# kibannISE2024_contral.net
KiCad netlist of a schematic drawn in EAGLE
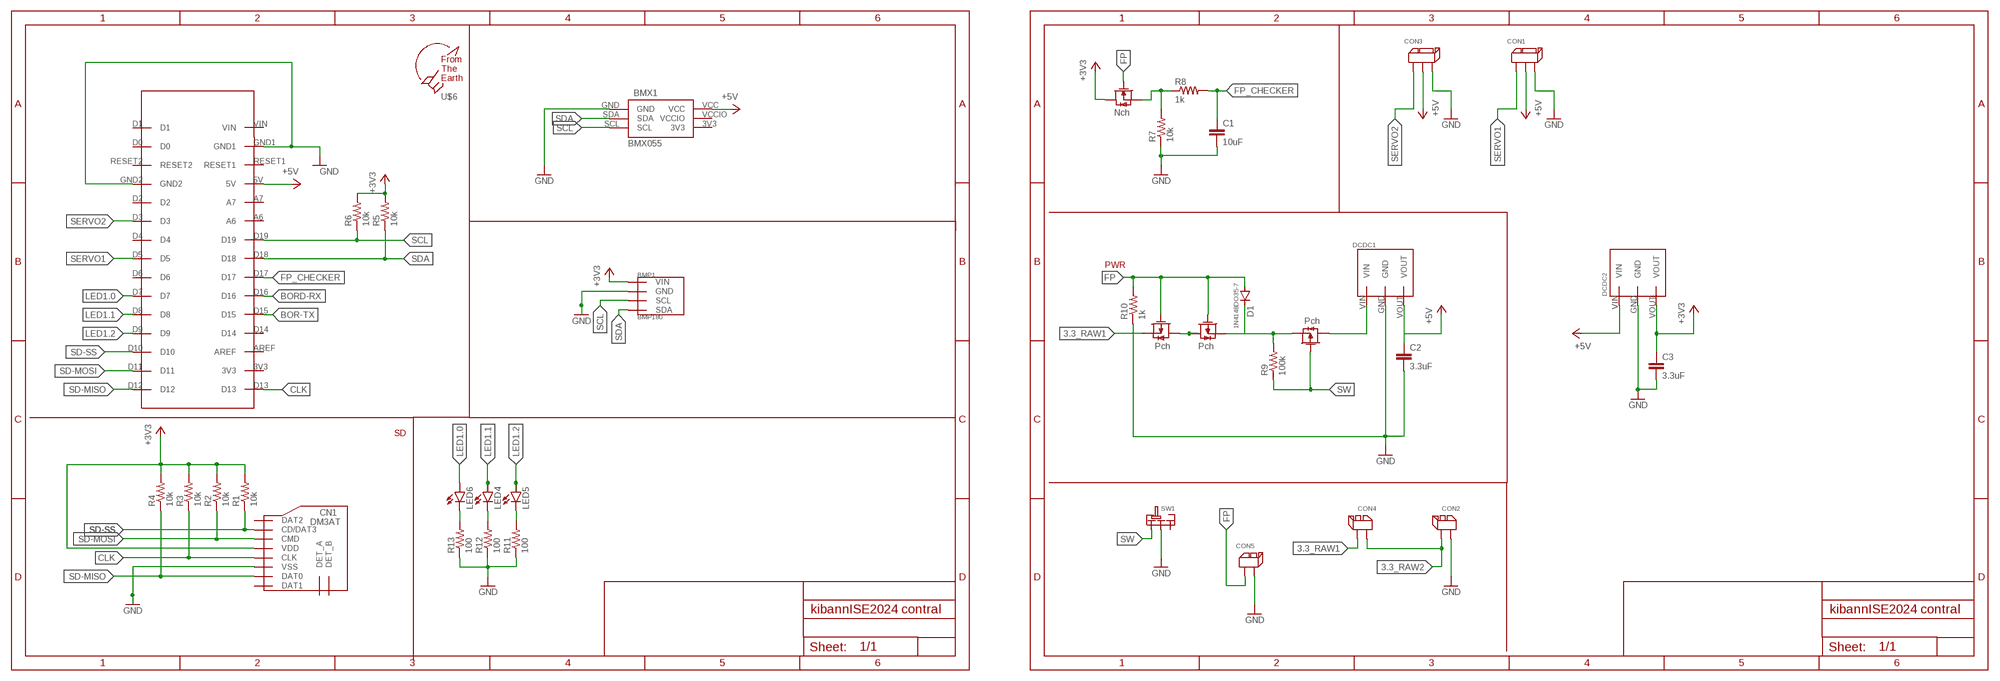
[diagram p0: schematic, sheet 1]

(export (version "E")
  (design (tool "Eeschema 10.0.6"))
  (components
    (comp (ref "BMP1")
      (value "BMP180")
      (footprint "eagle-import:GY-68")
      (libsource (lib "eagle-import") (part "BMP180"))
    )
    (comp (ref "BMX1")
      (value "BMX055")
      (footprint "eagle-import:BMX055")
      (libsource (lib "eagle-import") (part "BMX055"))
    )
    (comp (ref "C1")
      (value "10uF")
      (footprint "eagle-import:C025-024X044")
      (libsource (lib "eagle-import") (part "C-EU025-024X044"))
    )
    (comp (ref "C2")
      (value "3.3uF")
      (footprint "eagle-import:C025-024X044")
      (libsource (lib "eagle-import") (part "C-EU025-024X044"))
    )
    (comp (ref "C3")
      (value "3.3uF")
      (footprint "eagle-import:C025-024X044")
      (libsource (lib "eagle-import") (part "C-EU025-024X044"))
    )
    (comp (ref "CN1")
      (value "DM3AT")
      (footprint "eagle-import:DM3AT")
      (libsource (lib "eagle-import") (part "DM3AT"))
    )
    (comp (ref "CON1")
      (value "3PIN")
      (footprint "eagle-import:3PIN")
      (libsource (lib "eagle-import") (part "3PIN"))
    )
    (comp (ref "CON2")
      (value "2PIN")
      (footprint "eagle-import:2PIN")
      (libsource (lib "eagle-import") (part "2PIN"))
    )
    (comp (ref "CON3")
      (value "3PIN")
      (footprint "eagle-import:3PIN")
      (libsource (lib "eagle-import") (part "3PIN"))
    )
    (comp (ref "CON4")
      (value "2PIN")
      (footprint "eagle-import:2PIN")
      (libsource (lib "eagle-import") (part "2PIN"))
    )
    (comp (ref "CON5")
      (value "2PIN")
      (footprint "eagle-import:2PIN")
      (libsource (lib "eagle-import") (part "2PIN"))
    )
    (comp (ref "D1")
      (value "1N4148DO35-7")
      (footprint "eagle-import:DO35-7")
      (libsource (lib "eagle-import") (part "1N4148DO35-7"))
    )
    (comp (ref "DCDC1")
      (value "5V1A_M78AR05-1")
      (footprint "eagle-import:5V1A_M78AR05-1")
      (libsource (lib "eagle-import") (part "5V1A_M78AR05-1"))
    )
    (comp (ref "DCDC2")
      (value "3.3V1A_M78AR033-1")
      (footprint "eagle-import:3.3V1A_M78AR033-1")
      (libsource (lib "eagle-import") (part "3.3V1A_M78AR033-1"))
    )
    (comp (ref "LED4")
      (value "LED5MM")
      (footprint "eagle-import:LED5MM")
      (libsource (lib "eagle-import") (part "LED5MM"))
    )
    (comp (ref "LED5")
      (value "LED5MM")
      (footprint "eagle-import:LED5MM")
      (libsource (lib "eagle-import") (part "LED5MM"))
    )
    (comp (ref "LED6")
      (value "LED5MM")
      (footprint "eagle-import:LED5MM")
      (libsource (lib "eagle-import") (part "LED5MM"))
    )
    (comp (ref "R1")
      (value "10k")
      (footprint "eagle-import:0204_7")
      (libsource (lib "eagle-import") (part "R-US_0204/7"))
    )
    (comp (ref "R2")
      (value "10k")
      (footprint "eagle-import:0204_7")
      (libsource (lib "eagle-import") (part "R-US_0204/7"))
    )
    (comp (ref "R3")
      (value "10k")
      (footprint "eagle-import:0204_7")
      (libsource (lib "eagle-import") (part "R-US_0204/7"))
    )
    (comp (ref "R4")
      (value "10k")
      (footprint "eagle-import:0204_7")
      (libsource (lib "eagle-import") (part "R-US_0204/7"))
    )
    (comp (ref "R5")
      (value "10k")
      (footprint "eagle-import:0204_7")
      (libsource (lib "eagle-import") (part "R-US_0204/7"))
    )
    (comp (ref "R6")
      (value "10k")
      (footprint "eagle-import:0204_7")
      (libsource (lib "eagle-import") (part "R-US_0204/7"))
    )
    (comp (ref "R7")
      (value "10k")
      (footprint "eagle-import:0204_7")
      (libsource (lib "eagle-import") (part "R-US_0204/7"))
    )
    (comp (ref "R8")
      (value "1k")
      (footprint "eagle-import:0204_7")
      (libsource (lib "eagle-import") (part "R-US_0204/7"))
    )
    (comp (ref "R9")
      (value "100k")
      (footprint "eagle-import:0204_7")
      (libsource (lib "eagle-import") (part "R-US_0204/7"))
    )
    (comp (ref "R10")
      (value "1k")
      (footprint "eagle-import:0204_7")
      (libsource (lib "eagle-import") (part "R-US_0204/7"))
    )
    (comp (ref "R11")
      (value "100")
      (footprint "eagle-import:0204_7")
      (libsource (lib "eagle-import") (part "R-US_0204/7"))
    )
    (comp (ref "R12")
      (value "100")
      (footprint "eagle-import:0204_7")
      (libsource (lib "eagle-import") (part "R-US_0204/7"))
    )
    (comp (ref "R13")
      (value "100")
      (footprint "eagle-import:0204_7")
      (libsource (lib "eagle-import") (part "R-US_0204/7"))
    )
    (comp (ref "SW1")
      (value "SRIDE_SWITCH")
      (footprint "eagle-import:SRIDE_SWITCH")
      (libsource (lib "eagle-import") (part "SRIDE_SWITCH"))
    )
    (comp (ref "U$1")
      (value "ARDUINONANO")
      (footprint "eagle-import:ARDUINONANO")
      (libsource (lib "eagle-import") (part "ARDUINONANO"))
    )
    (comp (ref "U$2")
      (value "2SJ681-PCH")
      (footprint "eagle-import:2SJ681")
      (libsource (lib "eagle-import") (part "2SJ681-PCH"))
    )
    (comp (ref "U$3")
      (value "2SK4017-NCH")
      (footprint "eagle-import:2SK4017")
      (libsource (lib "eagle-import") (part "2SK4017-NCH"))
    )
    (comp (ref "U$4")
      (value "2SJ681-PCH")
      (footprint "eagle-import:2SJ681")
      (libsource (lib "eagle-import") (part "2SJ681-PCH"))
    )
    (comp (ref "U$5")
      (value "2SJ681-PCH")
      (footprint "eagle-import:2SJ681")
      (libsource (lib "eagle-import") (part "2SJ681-PCH"))
    )
    (comp (ref "U$6")
      (value "F.T.E.LOGO")
      (footprint "eagle-import:LOGO")
      (libsource (lib "eagle-import") (part "F.T.E.LOGO"))
    )
  )
  (nets
    (net (code "1") (name "+3V3") (class "Default")
      (node (ref "BMP1") (pin "P1") (pinfunction "VIN_P1") (pintype "bidirectional"))
      (node (ref "C3") (pin "1") (pinfunction "1_1") (pintype "passive"))
      (node (ref "CN1") (pin "VDD") (pinfunction "VDD_VDD") (pintype "bidirectional"))
      (node (ref "DCDC2") (pin "VOUT") (pinfunction "VOUT_VOUT") (pintype "bidirectional"))
      (node (ref "R1") (pin "2") (pinfunction "2_2") (pintype "passive"))
      (node (ref "R2") (pin "2") (pinfunction "2_2") (pintype "passive"))
      (node (ref "R3") (pin "2") (pinfunction "2_2") (pintype "passive"))
      (node (ref "R4") (pin "2") (pinfunction "2_2") (pintype "passive"))
      (node (ref "R5") (pin "2") (pinfunction "2_2") (pintype "passive"))
      (node (ref "R6") (pin "2") (pinfunction "2_2") (pintype "passive"))
      (node (ref "U$3") (pin "DRAIN") (pinfunction "DRAIN_DRAIN") (pintype "bidirectional"))
    )
    (net (code "2") (name "+5V") (class "Default")
      (node (ref "BMX1") (pin "VCC") (pinfunction "VCC_VCC") (pintype "power_in"))
      (node (ref "C2") (pin "1") (pinfunction "1_1") (pintype "passive"))
      (node (ref "CON1") (pin "P$2") (pinfunction "P$2_P$2") (pintype "bidirectional"))
      (node (ref "CON3") (pin "P$2") (pinfunction "P$2_P$2") (pintype "bidirectional"))
      (node (ref "DCDC1") (pin "VOUT") (pinfunction "VOUT_VOUT") (pintype "bidirectional"))
      (node (ref "DCDC2") (pin "VIN") (pinfunction "VIN_VIN") (pintype "bidirectional"))
      (node (ref "U$1") (pin "5V") (pinfunction "5V_5V") (pintype "bidirectional"))
    )
    (net (code "3") (name "/3V3") (class "Default")
      (node (ref "BMX1") (pin "3V3") (pinfunction "3V3_3V3") (pintype "power_in"))
    )
    (net (code "4") (name "/VCCIO") (class "Default")
      (node (ref "BMX1") (pin "VCCIO") (pinfunction "VCCIO_VCCIO") (pintype "power_in"))
    )
    (net (code "5") (name "3.3_RAW1") (class "Default")
      (node (ref "CON4") (pin "P$2") (pinfunction "P$2_P$2") (pintype "bidirectional"))
      (node (ref "U$2") (pin "SOURCE") (pinfunction "SOURCE_SOURCE") (pintype "bidirectional"))
    )
    (net (code "6") (name "3.3_RAW2") (class "Default")
      (node (ref "CON2") (pin "P$2") (pinfunction "P$2_P$2") (pintype "bidirectional"))
      (node (ref "CON4") (pin "P$1") (pinfunction "P$1_P$1") (pintype "bidirectional"))
    )
    (net (code "7") (name "BOR-TX") (class "Default")
      (node (ref "U$1") (pin "D15") (pinfunction "D15_D15") (pintype "bidirectional"))
    )
    (net (code "8") (name "BORD-RX") (class "Default")
      (node (ref "U$1") (pin "D16") (pinfunction "D16_D16") (pintype "bidirectional"))
    )
    (net (code "9") (name "CLK") (class "Default")
      (node (ref "CN1") (pin "CLK") (pinfunction "CLK_CLK") (pintype "bidirectional"))
      (node (ref "R3") (pin "1") (pinfunction "1_1") (pintype "passive"))
      (node (ref "U$1") (pin "D13") (pinfunction "D13_D13") (pintype "bidirectional"))
    )
    (net (code "10") (name "FP") (class "Default")
      (node (ref "CON5") (pin "P$1") (pinfunction "P$1_P$1") (pintype "bidirectional"))
      (node (ref "D1") (pin "A") (pinfunction "A_A") (pintype "passive"))
      (node (ref "R10") (pin "2") (pinfunction "2_2") (pintype "passive"))
      (node (ref "U$2") (pin "GATE") (pinfunction "GATE_GATE") (pintype "bidirectional"))
      (node (ref "U$3") (pin "GATE") (pinfunction "GATE_GATE") (pintype "bidirectional"))
      (node (ref "U$4") (pin "GATE") (pinfunction "GATE_GATE") (pintype "bidirectional"))
    )
    (net (code "11") (name "FP_CHECKER") (class "Default")
      (node (ref "C1") (pin "1") (pinfunction "1_1") (pintype "passive"))
      (node (ref "R8") (pin "2") (pinfunction "2_2") (pintype "passive"))
      (node (ref "U$1") (pin "D17") (pinfunction "D17_D17") (pintype "bidirectional"))
    )
    (net (code "12") (name "GND") (class "Default")
      (node (ref "BMP1") (pin "P2") (pinfunction "GND_P2") (pintype "bidirectional"))
      (node (ref "BMX1") (pin "GND") (pinfunction "GND_GND") (pintype "power_in"))
      (node (ref "C1") (pin "2") (pinfunction "2_2") (pintype "passive"))
      (node (ref "C2") (pin "2") (pinfunction "2_2") (pintype "passive"))
      (node (ref "C3") (pin "2") (pinfunction "2_2") (pintype "passive"))
      (node (ref "CN1") (pin "VSS") (pinfunction "VSS_VSS") (pintype "bidirectional"))
      (node (ref "CON1") (pin "P$3") (pinfunction "P$3_P$3") (pintype "bidirectional"))
      (node (ref "CON2") (pin "P$1") (pinfunction "P$1_P$1") (pintype "bidirectional"))
      (node (ref "CON3") (pin "P$3") (pinfunction "P$3_P$3") (pintype "bidirectional"))
      (node (ref "CON5") (pin "P$2") (pinfunction "P$2_P$2") (pintype "bidirectional"))
      (node (ref "DCDC1") (pin "GND") (pinfunction "GND_GND") (pintype "bidirectional"))
      (node (ref "DCDC2") (pin "GND") (pinfunction "GND_GND") (pintype "bidirectional"))
      (node (ref "R10") (pin "1") (pinfunction "1_1") (pintype "passive"))
      (node (ref "R11") (pin "1") (pinfunction "1_1") (pintype "passive"))
      (node (ref "R12") (pin "1") (pinfunction "1_1") (pintype "passive"))
      (node (ref "R13") (pin "1") (pinfunction "1_1") (pintype "passive"))
      (node (ref "R7") (pin "1") (pinfunction "1_1") (pintype "passive"))
      (node (ref "SW1") (pin "LR") (pinfunction "LR_LR") (pintype "bidirectional"))
      (node (ref "U$1") (pin "GND1") (pinfunction "GND1_GND1") (pintype "bidirectional"))
      (node (ref "U$1") (pin "GND2") (pinfunction "GND2_GND2") (pintype "bidirectional"))
    )
    (net (code "13") (name "LED1.0") (class "Default")
      (node (ref "LED6") (pin "A") (pinfunction "A_A") (pintype "passive"))
      (node (ref "U$1") (pin "D7") (pinfunction "D7_D7") (pintype "bidirectional"))
    )
    (net (code "14") (name "LED1.1") (class "Default")
      (node (ref "LED4") (pin "A") (pinfunction "A_A") (pintype "passive"))
      (node (ref "U$1") (pin "D8") (pinfunction "D8_D8") (pintype "bidirectional"))
    )
    (net (code "15") (name "LED1.2") (class "Default")
      (node (ref "LED5") (pin "A") (pinfunction "A_A") (pintype "passive"))
      (node (ref "U$1") (pin "D9") (pinfunction "D9_D9") (pintype "bidirectional"))
    )
    (net (code "16") (name "Net-(D1-PadC)") (class "Default")
      (node (ref "D1") (pin "C") (pinfunction "C_C") (pintype "passive"))
      (node (ref "R9") (pin "2") (pinfunction "2_2") (pintype "passive"))
      (node (ref "U$4") (pin "SOURCE") (pinfunction "SOURCE_SOURCE") (pintype "bidirectional"))
      (node (ref "U$5") (pin "SOURCE") (pinfunction "SOURCE_SOURCE") (pintype "bidirectional"))
    )
    (net (code "17") (name "Net-(DCDC1-PadVIN)") (class "Default")
      (node (ref "DCDC1") (pin "VIN") (pinfunction "VIN_VIN") (pintype "bidirectional"))
      (node (ref "U$5") (pin "DRAIN") (pinfunction "DRAIN_DRAIN") (pintype "bidirectional"))
    )
    (net (code "18") (name "Net-(LED4-C)") (class "Default")
      (node (ref "LED4") (pin "K") (pinfunction "C_K") (pintype "passive"))
      (node (ref "R12") (pin "2") (pinfunction "2_2") (pintype "passive"))
    )
    (net (code "19") (name "Net-(LED5-C)") (class "Default")
      (node (ref "LED5") (pin "K") (pinfunction "C_K") (pintype "passive"))
      (node (ref "R11") (pin "2") (pinfunction "2_2") (pintype "passive"))
    )
    (net (code "20") (name "Net-(LED6-C)") (class "Default")
      (node (ref "LED6") (pin "K") (pinfunction "C_K") (pintype "passive"))
      (node (ref "R13") (pin "2") (pinfunction "2_2") (pintype "passive"))
    )
    (net (code "21") (name "Net-(R7-Pad2)") (class "Default")
      (node (ref "R7") (pin "2") (pinfunction "2_2") (pintype "passive"))
      (node (ref "R8") (pin "1") (pinfunction "1_1") (pintype "passive"))
      (node (ref "U$3") (pin "SOURCE") (pinfunction "SOURCE_SOURCE") (pintype "bidirectional"))
    )
    (net (code "22") (name "Net-(U$2-PadDRAIN)") (class "Default")
      (node (ref "U$2") (pin "DRAIN") (pinfunction "DRAIN_DRAIN") (pintype "bidirectional"))
      (node (ref "U$4") (pin "DRAIN") (pinfunction "DRAIN_DRAIN") (pintype "bidirectional"))
    )
    (net (code "23") (name "SCL") (class "Default")
      (node (ref "BMP1") (pin "P3") (pinfunction "SCL_P3") (pintype "bidirectional"))
      (node (ref "BMX1") (pin "SCL") (pinfunction "SCL_SCL") (pintype "bidirectional"))
      (node (ref "R6") (pin "1") (pinfunction "1_1") (pintype "passive"))
      (node (ref "U$1") (pin "D19") (pinfunction "D19_D19") (pintype "bidirectional"))
    )
    (net (code "24") (name "SD-MISO") (class "Default")
      (node (ref "CN1") (pin "DAT0") (pinfunction "DAT0_DAT0") (pintype "bidirectional"))
      (node (ref "R4") (pin "1") (pinfunction "1_1") (pintype "passive"))
      (node (ref "U$1") (pin "D12") (pinfunction "D12_D12") (pintype "bidirectional"))
    )
    (net (code "25") (name "SD-MOSI") (class "Default")
      (node (ref "CN1") (pin "CMD") (pinfunction "CMD_CMD") (pintype "bidirectional"))
      (node (ref "R2") (pin "1") (pinfunction "1_1") (pintype "passive"))
      (node (ref "U$1") (pin "D11") (pinfunction "D11_D11") (pintype "bidirectional"))
    )
    (net (code "26") (name "SD-SS") (class "Default")
      (node (ref "CN1") (pin "CD/DAT3") (pinfunction "CD/DAT3_CD/DAT3") (pintype "bidirectional"))
      (node (ref "R1") (pin "1") (pinfunction "1_1") (pintype "passive"))
      (node (ref "U$1") (pin "D10") (pinfunction "D10_D10") (pintype "bidirectional"))
    )
    (net (code "27") (name "SDA") (class "Default")
      (node (ref "BMP1") (pin "P4") (pinfunction "SDA_P4") (pintype "bidirectional"))
      (node (ref "BMX1") (pin "SDA") (pinfunction "SDA_SDA") (pintype "bidirectional"))
      (node (ref "R5") (pin "1") (pinfunction "1_1") (pintype "passive"))
      (node (ref "U$1") (pin "D18") (pinfunction "D18_D18") (pintype "bidirectional"))
    )
    (net (code "28") (name "SERVO1") (class "Default")
      (node (ref "CON1") (pin "P$1") (pinfunction "P$1_P$1") (pintype "bidirectional"))
      (node (ref "U$1") (pin "D5") (pinfunction "D5_D5") (pintype "bidirectional"))
    )
    (net (code "29") (name "SERVO2") (class "Default")
      (node (ref "CON3") (pin "P$1") (pinfunction "P$1_P$1") (pintype "bidirectional"))
      (node (ref "U$1") (pin "D3") (pinfunction "D3_D3") (pintype "bidirectional"))
    )
    (net (code "30") (name "SW") (class "Default")
      (node (ref "R9") (pin "1") (pinfunction "1_1") (pintype "passive"))
      (node (ref "SW1") (pin "L") (pinfunction "L_L") (pintype "bidirectional"))
      (node (ref "U$5") (pin "GATE") (pinfunction "GATE_GATE") (pintype "bidirectional"))
    )
    (net (code "31") (name "unconnected-(CN1-PadDAT1)") (class "Default")
      (node (ref "CN1") (pin "DAT1") (pinfunction "DAT1_DAT1") (pintype "bidirectional"))
    )
    (net (code "32") (name "unconnected-(CN1-PadDAT2)") (class "Default")
      (node (ref "CN1") (pin "DAT2") (pinfunction "DAT2_DAT2") (pintype "bidirectional"))
    )
    (net (code "33") (name "unconnected-(CN1-PadDET_A)") (class "Default")
      (node (ref "CN1") (pin "DET_A") (pinfunction "DET_A_DET_A") (pintype "bidirectional"))
    )
    (net (code "34") (name "unconnected-(CN1-PadDET_B)") (class "Default")
      (node (ref "CN1") (pin "DET_B") (pinfunction "DET_B_DET_B") (pintype "bidirectional"))
    )
    (net (code "35") (name "unconnected-(SW1-PadR)") (class "Default")
      (node (ref "SW1") (pin "R") (pinfunction "R_R") (pintype "bidirectional"))
    )
    (net (code "36") (name "unconnected-(U$1-Pad3V3)") (class "Default")
      (node (ref "U$1") (pin "3V3") (pinfunction "3V3_3V3") (pintype "bidirectional"))
    )
    (net (code "37") (name "unconnected-(U$1-PadA6)") (class "Default")
      (node (ref "U$1") (pin "A6") (pinfunction "A6_A6") (pintype "bidirectional"))
    )
    (net (code "38") (name "unconnected-(U$1-PadA7)") (class "Default")
      (node (ref "U$1") (pin "A7") (pinfunction "A7_A7") (pintype "bidirectional"))
    )
    (net (code "39") (name "unconnected-(U$1-PadAREF)") (class "Default")
      (node (ref "U$1") (pin "AREF") (pinfunction "AREF_AREF") (pintype "bidirectional"))
    )
    (net (code "40") (name "unconnected-(U$1-PadD0)") (class "Default")
      (node (ref "U$1") (pin "D0") (pinfunction "D0_D0") (pintype "bidirectional"))
    )
    (net (code "41") (name "unconnected-(U$1-PadD1)") (class "Default")
      (node (ref "U$1") (pin "D1") (pinfunction "D1_D1") (pintype "bidirectional"))
    )
    (net (code "42") (name "unconnected-(U$1-PadD2)") (class "Default")
      (node (ref "U$1") (pin "D2") (pinfunction "D2_D2") (pintype "bidirectional"))
    )
    (net (code "43") (name "unconnected-(U$1-PadD4)") (class "Default")
      (node (ref "U$1") (pin "D4") (pinfunction "D4_D4") (pintype "bidirectional"))
    )
    (net (code "44") (name "unconnected-(U$1-PadD6)") (class "Default")
      (node (ref "U$1") (pin "D6") (pinfunction "D6_D6") (pintype "bidirectional"))
    )
    (net (code "45") (name "unconnected-(U$1-PadD14)") (class "Default")
      (node (ref "U$1") (pin "D14") (pinfunction "D14_D14") (pintype "bidirectional"))
    )
    (net (code "46") (name "unconnected-(U$1-PadRESET1)") (class "Default")
      (node (ref "U$1") (pin "RESET1") (pinfunction "RESET1_RESET1") (pintype "bidirectional"))
    )
    (net (code "47") (name "unconnected-(U$1-PadRESET2)") (class "Default")
      (node (ref "U$1") (pin "RESET2") (pinfunction "RESET2_RESET2") (pintype "bidirectional"))
    )
    (net (code "48") (name "unconnected-(U$1-PadVIN)") (class "Default")
      (node (ref "U$1") (pin "VIN") (pinfunction "VIN_VIN") (pintype "bidirectional"))
    )
  )
)
